# controller.net
KiCad netlist of a schematic drawn in Altium Designer
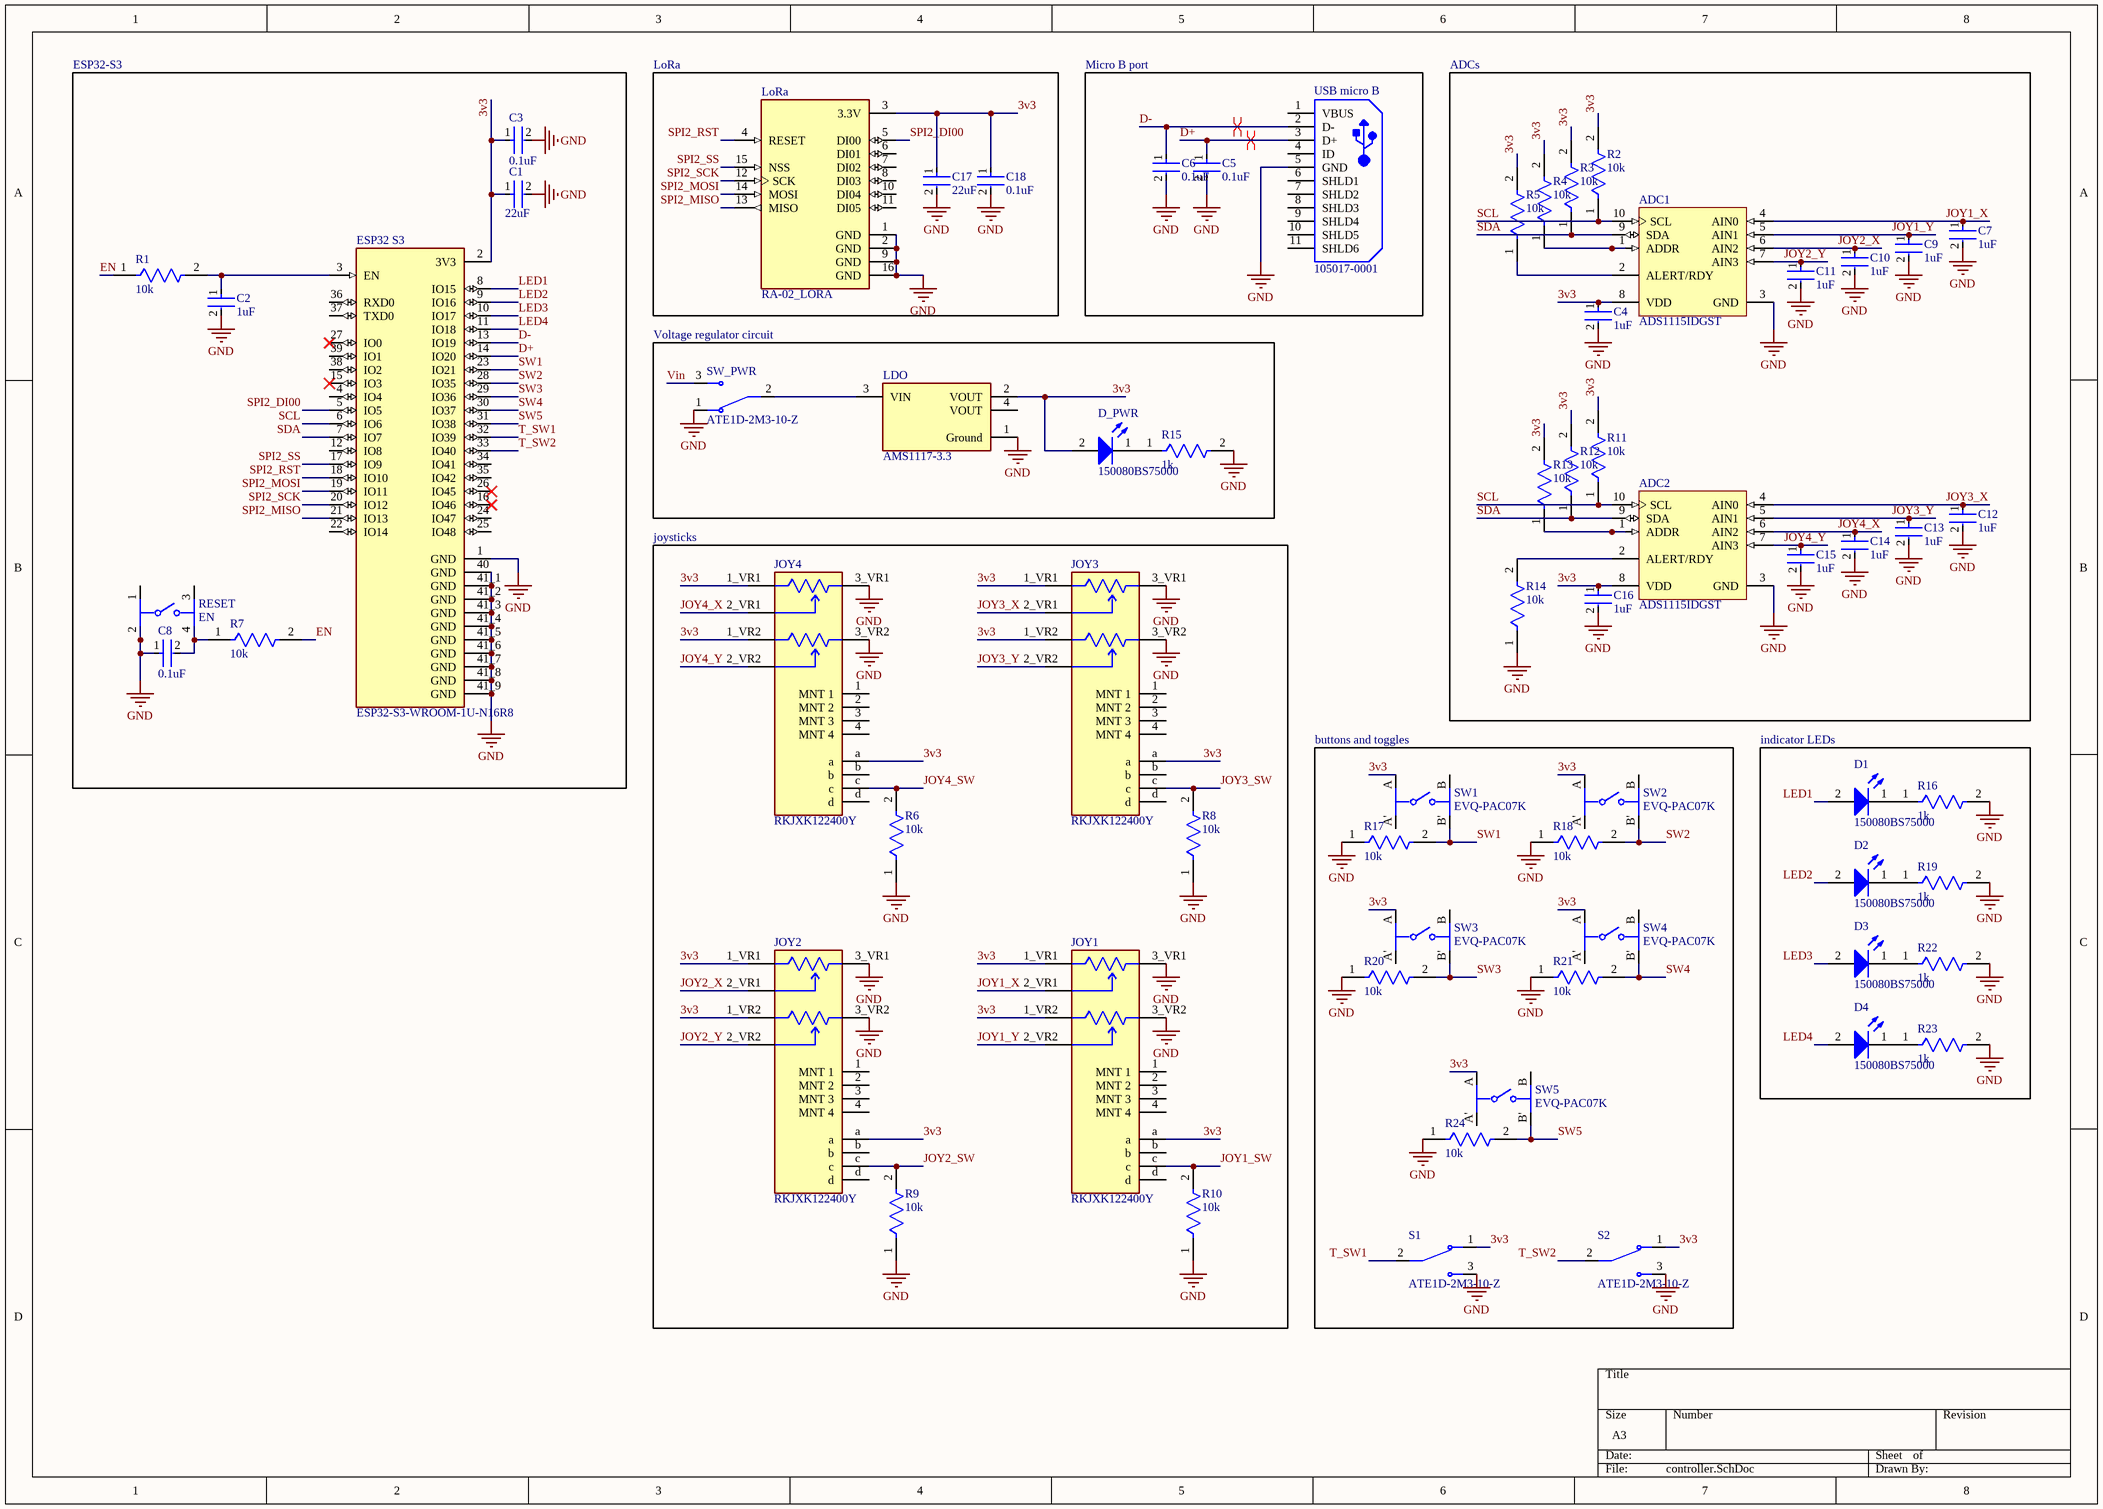
[diagram p0: controller.SchDoc]

(export (version "E")
  (design (tool "Eeschema 10.0.6"))
  (components
    (comp (ref "ADC1")
      (value "ADS1115IDGST")
      (footprint "TI-DGS10_M")
      (fields (field (name "MANUFACTURER") "Texas Instruments"))
      (libsource (lib "Altium Content Vault") (part "TI-ADS1015_1115-10"))
    )
    (comp (ref "ADC2")
      (value "ADS1115IDGST")
      (footprint "TI-DGS10_M")
      (fields (field (name "MANUFACTURER") "Texas Instruments"))
      (libsource (lib "Altium Content Vault") (part "TI-ADS1015_1115-10"))
    )
    (comp (ref "C1")
      (value "22uF")
      (footprint "FP-0805-L_2_01_0_2-W_1_25-IPC_B")
      (description "General Purpose Ceramic Capacitor, 0805, 22uF, 20%, X5R, 15%, 6.3V")
      (fields (field (name "TOLERANCE") "20%") (field (name "VOLTAGE") "6.3V"))
      (libsource (lib "Altium Content Vault") (part "02cd4be3c70576c341d710602a673aa"))
    )
    (comp (ref "C2")
      (value "1uF")
      (footprint "FP-0805-L_2_01_0_2-W_1_25-IPC_B")
      (description "General Purpose Ceramic Capacitor, 0805, 1uF, 10%, X7R, 15%, 25V")
      (fields (field (name "TOLERANCE") "10%") (field (name "VOLTAGE") "25V"))
      (libsource (lib "Altium Content Vault") (part "b4654b650e69147ec39a6b967a45e02"))
    )
    (comp (ref "C3")
      (value "0.1uF")
      (footprint "FP-0805-L_2_01_0_2-W_1_25-IPC_C")
      (description "General Purpose Ceramic Capacitor, 0805, 100nF, 10%, X7R, 0.15, 50V")
      (fields (field (name "TOLERANCE") "10%") (field (name "VOLTAGE") "50V"))
      (libsource (lib "Altium Content Vault") (part "02cd4be3c70576c341d710602a673aa"))
    )
    (comp (ref "C4")
      (value "1uF")
      (footprint "FP-0805-L_2_01_0_2-W_1_25-IPC_B")
      (description "General Purpose Ceramic Capacitor, 0805, 1uF, 10%, X7R, 15%, 25V")
      (fields (field (name "TOLERANCE") "10%") (field (name "VOLTAGE") "25V"))
      (libsource (lib "Altium Content Vault") (part "b4654b650e69147ec39a6b967a45e02"))
    )
    (comp (ref "C5")
      (value "0.1uF")
      (footprint "FP-0805-L_2_01_0_2-W_1_25-IPC_C")
      (description "General Purpose Ceramic Capacitor, 0805, 100nF, 10%, X7R, 0.15, 50V")
      (fields (field (name "TOLERANCE") "10%") (field (name "VOLTAGE") "50V"))
      (libsource (lib "Altium Content Vault") (part "02cd4be3c70576c341d710602a673aa"))
    )
    (comp (ref "C6")
      (value "0.1uF")
      (footprint "FP-0805-L_2_01_0_2-W_1_25-IPC_C")
      (description "General Purpose Ceramic Capacitor, 0805, 100nF, 10%, X7R, 0.15, 50V")
      (fields (field (name "TOLERANCE") "10%") (field (name "VOLTAGE") "50V"))
      (libsource (lib "Altium Content Vault") (part "02cd4be3c70576c341d710602a673aa"))
    )
    (comp (ref "C7")
      (value "1uF")
      (footprint "FP-0805-L_2_01_0_2-W_1_25-IPC_B")
      (description "General Purpose Ceramic Capacitor, 0805, 1uF, 10%, X7R, 15%, 25V")
      (fields (field (name "TOLERANCE") "10%") (field (name "VOLTAGE") "25V"))
      (libsource (lib "Altium Content Vault") (part "b4654b650e69147ec39a6b967a45e02"))
    )
    (comp (ref "C8")
      (value "0.1uF")
      (footprint "FP-0805-L_2_01_0_2-W_1_25-IPC_C")
      (description "General Purpose Ceramic Capacitor, 0805, 100nF, 10%, X7R, 0.15, 50V")
      (fields (field (name "TOLERANCE") "10%") (field (name "VOLTAGE") "50V"))
      (libsource (lib "Altium Content Vault") (part "02cd4be3c70576c341d710602a673aa"))
    )
    (comp (ref "C9")
      (value "1uF")
      (footprint "FP-0805-L_2_01_0_2-W_1_25-IPC_B")
      (description "General Purpose Ceramic Capacitor, 0805, 1uF, 10%, X7R, 15%, 25V")
      (fields (field (name "TOLERANCE") "10%") (field (name "VOLTAGE") "25V"))
      (libsource (lib "Altium Content Vault") (part "b4654b650e69147ec39a6b967a45e02"))
    )
    (comp (ref "C10")
      (value "1uF")
      (footprint "FP-0805-L_2_01_0_2-W_1_25-IPC_B")
      (description "General Purpose Ceramic Capacitor, 0805, 1uF, 10%, X7R, 15%, 25V")
      (fields (field (name "TOLERANCE") "10%") (field (name "VOLTAGE") "25V"))
      (libsource (lib "Altium Content Vault") (part "b4654b650e69147ec39a6b967a45e02"))
    )
    (comp (ref "C11")
      (value "1uF")
      (footprint "FP-0805-L_2_01_0_2-W_1_25-IPC_B")
      (description "General Purpose Ceramic Capacitor, 0805, 1uF, 10%, X7R, 15%, 25V")
      (fields (field (name "TOLERANCE") "10%") (field (name "VOLTAGE") "25V"))
      (libsource (lib "Altium Content Vault") (part "b4654b650e69147ec39a6b967a45e02"))
    )
    (comp (ref "C12")
      (value "1uF")
      (footprint "FP-0805-L_2_01_0_2-W_1_25-IPC_B")
      (description "General Purpose Ceramic Capacitor, 0805, 1uF, 10%, X7R, 15%, 25V")
      (fields (field (name "TOLERANCE") "10%") (field (name "VOLTAGE") "25V"))
      (libsource (lib "Altium Content Vault") (part "b4654b650e69147ec39a6b967a45e02"))
    )
    (comp (ref "C13")
      (value "1uF")
      (footprint "FP-0805-L_2_01_0_2-W_1_25-IPC_B")
      (description "General Purpose Ceramic Capacitor, 0805, 1uF, 10%, X7R, 15%, 25V")
      (fields (field (name "TOLERANCE") "10%") (field (name "VOLTAGE") "25V"))
      (libsource (lib "Altium Content Vault") (part "b4654b650e69147ec39a6b967a45e02"))
    )
    (comp (ref "C14")
      (value "1uF")
      (footprint "FP-0805-L_2_01_0_2-W_1_25-IPC_B")
      (description "General Purpose Ceramic Capacitor, 0805, 1uF, 10%, X7R, 15%, 25V")
      (fields (field (name "TOLERANCE") "10%") (field (name "VOLTAGE") "25V"))
      (libsource (lib "Altium Content Vault") (part "b4654b650e69147ec39a6b967a45e02"))
    )
    (comp (ref "C15")
      (value "1uF")
      (footprint "FP-0805-L_2_01_0_2-W_1_25-IPC_B")
      (description "General Purpose Ceramic Capacitor, 0805, 1uF, 10%, X7R, 15%, 25V")
      (fields (field (name "TOLERANCE") "10%") (field (name "VOLTAGE") "25V"))
      (libsource (lib "Altium Content Vault") (part "b4654b650e69147ec39a6b967a45e02"))
    )
    (comp (ref "C16")
      (value "1uF")
      (footprint "FP-0805-L_2_01_0_2-W_1_25-IPC_B")
      (description "General Purpose Ceramic Capacitor, 0805, 1uF, 10%, X7R, 15%, 25V")
      (fields (field (name "TOLERANCE") "10%") (field (name "VOLTAGE") "25V"))
      (libsource (lib "Altium Content Vault") (part "b4654b650e69147ec39a6b967a45e02"))
    )
    (comp (ref "C17")
      (value "22uF")
      (footprint "FP-0805-L_2_01_0_2-W_1_25-IPC_B")
      (description "General Purpose Ceramic Capacitor, 0805, 22uF, 20%, X5R, 15%, 6.3V")
      (fields (field (name "TOLERANCE") "20%") (field (name "VOLTAGE") "6.3V"))
      (libsource (lib "Altium Content Vault") (part "02cd4be3c70576c341d710602a673aa"))
    )
    (comp (ref "C18")
      (value "0.1uF")
      (footprint "FP-0805-L_2_01_0_2-W_1_25-IPC_C")
      (description "General Purpose Ceramic Capacitor, 0805, 100nF, 10%, X7R, 0.15, 50V")
      (fields (field (name "TOLERANCE") "10%") (field (name "VOLTAGE") "50V"))
      (libsource (lib "Altium Content Vault") (part "02cd4be3c70576c341d710602a673aa"))
    )
    (comp (ref "D1")
      (value "150080BS75000")
      (footprint "WL-SMCW_0805_150080xx75000")
      (description "Led, Blue, 470 Nm, 3.2 V, 30 Ma, 145 Mcd Rohs Compliant: Yes")
      (libsource (lib "Altium Content Vault") (part "LED_Blue_2A-1K"))
    )
    (comp (ref "D2")
      (value "150080BS75000")
      (footprint "WL-SMCW_0805_150080xx75000")
      (description "Led, Blue, 470 Nm, 3.2 V, 30 Ma, 145 Mcd Rohs Compliant: Yes")
      (libsource (lib "Altium Content Vault") (part "LED_Blue_2A-1K"))
    )
    (comp (ref "D3")
      (value "150080BS75000")
      (footprint "WL-SMCW_0805_150080xx75000")
      (description "Led, Blue, 470 Nm, 3.2 V, 30 Ma, 145 Mcd Rohs Compliant: Yes")
      (libsource (lib "Altium Content Vault") (part "LED_Blue_2A-1K"))
    )
    (comp (ref "D4")
      (value "150080BS75000")
      (footprint "WL-SMCW_0805_150080xx75000")
      (description "Led, Blue, 470 Nm, 3.2 V, 30 Ma, 145 Mcd Rohs Compliant: Yes")
      (libsource (lib "Altium Content Vault") (part "LED_Blue_2A-1K"))
    )
    (comp (ref "D_PWR")
      (value "150080BS75000")
      (footprint "WL-SMCW_0805_150080xx75000")
      (description "Led, Blue, 470 Nm, 3.2 V, 30 Ma, 145 Mcd Rohs Compliant: Yes")
      (libsource (lib "Altium Content Vault") (part "LED_Blue_2A-1K"))
    )
    (comp (ref "ESP32 S3")
      (value "ESP32-S3-WROOM-1U-N16R8")
      (footprint "XCVR_ESP32-S3-WROOM-1U-N16R8")
      (fields (field (name "MF") "Espressif Systems"))
      (libsource (lib "ESP32-S3-WROOM-1U-N16R8") (part "ESP32-S3-WROOM-1U-N16R8"))
    )
    (comp (ref "JOY1")
      (value "RKJXK122400Y")
      (footprint "FP-RKJXK122400Y-MFG")
      (description "Res POT 10K Ohm 0.0125W (25.4 X 20.7 X 19.3mm) Pin Bracket Mount/Through Hole Tray")
      (libsource (lib "Altium Content Vault") (part "63a56dd8e99e1e1552a3870b2e96c5c"))
    )
    (comp (ref "JOY2")
      (value "RKJXK122400Y")
      (footprint "FP-RKJXK122400Y-MFG")
      (description "Res POT 10K Ohm 0.0125W (25.4 X 20.7 X 19.3mm) Pin Bracket Mount/Through Hole Tray")
      (libsource (lib "Altium Content Vault") (part "63a56dd8e99e1e1552a3870b2e96c5c"))
    )
    (comp (ref "JOY3")
      (value "RKJXK122400Y")
      (footprint "FP-RKJXK122400Y-MFG")
      (description "Res POT 10K Ohm 0.0125W (25.4 X 20.7 X 19.3mm) Pin Bracket Mount/Through Hole Tray")
      (libsource (lib "Altium Content Vault") (part "63a56dd8e99e1e1552a3870b2e96c5c"))
    )
    (comp (ref "JOY4")
      (value "RKJXK122400Y")
      (footprint "FP-RKJXK122400Y-MFG")
      (description "Res POT 10K Ohm 0.0125W (25.4 X 20.7 X 19.3mm) Pin Bracket Mount/Through Hole Tray")
      (libsource (lib "Altium Content Vault") (part "63a56dd8e99e1e1552a3870b2e96c5c"))
    )
    (comp (ref "LDO")
      (value "AMS1117-3.3")
      (footprint "FP-AMS1117-IPC_C")
      (description "LDO Voltage Regulators 1A, 3.3V")
      (fields
        (field (name "OCTOPART") "https://octopart.com/ams1117-3.3-advanced+monolithic+systems-25899300")
        (field (name "MANUFACTURER") "Advanced Monolithic Systems")
      )
      (libsource (lib "Altium Content Vault") (part "8bdbb5f8e77002000e30dd2845d0354"))
    )
    (comp (ref "LoRa")
      (value "RA-02_LORA")
      (footprint "MODULE_RA-02_LORA")
      (description "Ra-02 LoRa RF M5Stack Platform Evaluation Expansion Board")
      (libsource (lib "RA-02_LORA") (part "RA-02_LORA"))
    )
    (comp (ref "R1")
      (value "10k")
      (footprint "FP-CRCW0805-e3-IPC_A")
      (description "RES Thick Film, 10kΩ, 1%, 0.125W, 100ppm/°C, 0805")
      (fields (field (name "TOLERANCE") "1%"))
      (libsource (lib "Altium Content Vault") (part "1029c3af85768c4190bb7ad29bc67b5"))
    )
    (comp (ref "R2")
      (value "10k")
      (footprint "FP-CRCW0805-e3-IPC_A")
      (description "RES Thick Film, 10kΩ, 1%, 0.125W, 100ppm/°C, 0805")
      (fields (field (name "TOLERANCE") "1%"))
      (libsource (lib "Altium Content Vault") (part "1029c3af85768c4190bb7ad29bc67b5"))
    )
    (comp (ref "R3")
      (value "10k")
      (footprint "FP-CRCW0805-e3-IPC_A")
      (description "RES Thick Film, 10kΩ, 1%, 0.125W, 100ppm/°C, 0805")
      (fields (field (name "TOLERANCE") "1%"))
      (libsource (lib "Altium Content Vault") (part "1029c3af85768c4190bb7ad29bc67b5"))
    )
    (comp (ref "R4")
      (value "10k")
      (footprint "FP-CRCW0805-e3-IPC_A")
      (description "RES Thick Film, 10kΩ, 1%, 0.125W, 100ppm/°C, 0805")
      (fields (field (name "TOLERANCE") "1%"))
      (libsource (lib "Altium Content Vault") (part "1029c3af85768c4190bb7ad29bc67b5"))
    )
    (comp (ref "R5")
      (value "10k")
      (footprint "FP-CRCW0805-e3-IPC_A")
      (description "RES Thick Film, 10kΩ, 1%, 0.125W, 100ppm/°C, 0805")
      (fields (field (name "TOLERANCE") "1%"))
      (libsource (lib "Altium Content Vault") (part "1029c3af85768c4190bb7ad29bc67b5"))
    )
    (comp (ref "R6")
      (value "10k")
      (footprint "FP-CRCW0805-e3-IPC_A")
      (description "RES Thick Film, 10kΩ, 1%, 0.125W, 100ppm/°C, 0805")
      (fields (field (name "TOLERANCE") "1%"))
      (libsource (lib "Altium Content Vault") (part "1029c3af85768c4190bb7ad29bc67b5"))
    )
    (comp (ref "R7")
      (value "10k")
      (footprint "FP-CRCW0805-e3-IPC_A")
      (description "RES Thick Film, 10kΩ, 1%, 0.125W, 100ppm/°C, 0805")
      (fields (field (name "TOLERANCE") "1%"))
      (libsource (lib "Altium Content Vault") (part "1029c3af85768c4190bb7ad29bc67b5"))
    )
    (comp (ref "R8")
      (value "10k")
      (footprint "FP-CRCW0805-e3-IPC_A")
      (description "RES Thick Film, 10kΩ, 1%, 0.125W, 100ppm/°C, 0805")
      (fields (field (name "TOLERANCE") "1%"))
      (libsource (lib "Altium Content Vault") (part "1029c3af85768c4190bb7ad29bc67b5"))
    )
    (comp (ref "R9")
      (value "10k")
      (footprint "FP-CRCW0805-e3-IPC_A")
      (description "RES Thick Film, 10kΩ, 1%, 0.125W, 100ppm/°C, 0805")
      (fields (field (name "TOLERANCE") "1%"))
      (libsource (lib "Altium Content Vault") (part "1029c3af85768c4190bb7ad29bc67b5"))
    )
    (comp (ref "R10")
      (value "10k")
      (footprint "FP-CRCW0805-e3-IPC_A")
      (description "RES Thick Film, 10kΩ, 1%, 0.125W, 100ppm/°C, 0805")
      (fields (field (name "TOLERANCE") "1%"))
      (libsource (lib "Altium Content Vault") (part "1029c3af85768c4190bb7ad29bc67b5"))
    )
    (comp (ref "R11")
      (value "10k")
      (footprint "FP-CRCW0805-e3-IPC_A")
      (description "RES Thick Film, 10kΩ, 1%, 0.125W, 100ppm/°C, 0805")
      (fields (field (name "TOLERANCE") "1%"))
      (libsource (lib "Altium Content Vault") (part "1029c3af85768c4190bb7ad29bc67b5"))
    )
    (comp (ref "R12")
      (value "10k")
      (footprint "FP-CRCW0805-e3-IPC_A")
      (description "RES Thick Film, 10kΩ, 1%, 0.125W, 100ppm/°C, 0805")
      (fields (field (name "TOLERANCE") "1%"))
      (libsource (lib "Altium Content Vault") (part "1029c3af85768c4190bb7ad29bc67b5"))
    )
    (comp (ref "R13")
      (value "10k")
      (footprint "FP-CRCW0805-e3-IPC_A")
      (description "RES Thick Film, 10kΩ, 1%, 0.125W, 100ppm/°C, 0805")
      (fields (field (name "TOLERANCE") "1%"))
      (libsource (lib "Altium Content Vault") (part "1029c3af85768c4190bb7ad29bc67b5"))
    )
    (comp (ref "R14")
      (value "10k")
      (footprint "FP-CRCW0805-e3-IPC_A")
      (description "RES Thick Film, 10kΩ, 1%, 0.125W, 100ppm/°C, 0805")
      (fields (field (name "TOLERANCE") "1%"))
      (libsource (lib "Altium Content Vault") (part "1029c3af85768c4190bb7ad29bc67b5"))
    )
    (comp (ref "R15")
      (value "1k")
      (footprint "FP-CRCW0805-e3-MFG")
      (description "RES Thick Film, 1.2kΩ, 1%, 0.125W, 100ppm/°C, 0805")
      (fields (field (name "TOLERANCE") "1%"))
      (libsource (lib "Altium Content Vault") (part "1029c3af85768c4190bb7ad29bc67b5"))
    )
    (comp (ref "R16")
      (value "1k")
      (footprint "FP-CRCW0805-e3-MFG")
      (description "RES Thick Film, 1.2kΩ, 1%, 0.125W, 100ppm/°C, 0805")
      (fields (field (name "TOLERANCE") "1%"))
      (libsource (lib "Altium Content Vault") (part "1029c3af85768c4190bb7ad29bc67b5"))
    )
    (comp (ref "R17")
      (value "10k")
      (footprint "FP-CRCW0805-e3-IPC_A")
      (description "RES Thick Film, 10kΩ, 1%, 0.125W, 100ppm/°C, 0805")
      (fields (field (name "TOLERANCE") "1%"))
      (libsource (lib "Altium Content Vault") (part "1029c3af85768c4190bb7ad29bc67b5"))
    )
    (comp (ref "R18")
      (value "10k")
      (footprint "FP-CRCW0805-e3-IPC_A")
      (description "RES Thick Film, 10kΩ, 1%, 0.125W, 100ppm/°C, 0805")
      (fields (field (name "TOLERANCE") "1%"))
      (libsource (lib "Altium Content Vault") (part "1029c3af85768c4190bb7ad29bc67b5"))
    )
    (comp (ref "R19")
      (value "1k")
      (footprint "FP-CRCW0805-e3-MFG")
      (description "RES Thick Film, 1.2kΩ, 1%, 0.125W, 100ppm/°C, 0805")
      (fields (field (name "TOLERANCE") "1%"))
      (libsource (lib "Altium Content Vault") (part "1029c3af85768c4190bb7ad29bc67b5"))
    )
    (comp (ref "R20")
      (value "10k")
      (footprint "FP-CRCW0805-e3-IPC_A")
      (description "RES Thick Film, 10kΩ, 1%, 0.125W, 100ppm/°C, 0805")
      (fields (field (name "TOLERANCE") "1%"))
      (libsource (lib "Altium Content Vault") (part "1029c3af85768c4190bb7ad29bc67b5"))
    )
    (comp (ref "R21")
      (value "10k")
      (footprint "FP-CRCW0805-e3-IPC_A")
      (description "RES Thick Film, 10kΩ, 1%, 0.125W, 100ppm/°C, 0805")
      (fields (field (name "TOLERANCE") "1%"))
      (libsource (lib "Altium Content Vault") (part "1029c3af85768c4190bb7ad29bc67b5"))
    )
    (comp (ref "R22")
      (value "1k")
      (footprint "FP-CRCW0805-e3-MFG")
      (description "RES Thick Film, 1.2kΩ, 1%, 0.125W, 100ppm/°C, 0805")
      (fields (field (name "TOLERANCE") "1%"))
      (libsource (lib "Altium Content Vault") (part "1029c3af85768c4190bb7ad29bc67b5"))
    )
    (comp (ref "R23")
      (value "1k")
      (footprint "FP-CRCW0805-e3-MFG")
      (description "RES Thick Film, 1.2kΩ, 1%, 0.125W, 100ppm/°C, 0805")
      (fields (field (name "TOLERANCE") "1%"))
      (libsource (lib "Altium Content Vault") (part "1029c3af85768c4190bb7ad29bc67b5"))
    )
    (comp (ref "R24")
      (value "10k")
      (footprint "FP-CRCW0805-e3-IPC_A")
      (description "RES Thick Film, 10kΩ, 1%, 0.125W, 100ppm/°C, 0805")
      (fields (field (name "TOLERANCE") "1%"))
      (libsource (lib "Altium Content Vault") (part "1029c3af85768c4190bb7ad29bc67b5"))
    )
    (comp (ref "RESET")
      (value "EN")
      (footprint "FP-FSM2JSMAA-MFG")
      (description "SWITCH TACTILE SPST-NO 0.05A 24V")
      (fields
        (field (name "MANUFACTURER PART NUMBER") "FSM2JSMAA")
        (field (name "MANUFACTURER") "TE Connectivity")
      )
      (libsource (lib "Altium Content Vault") (part "b8895f3f4cefb76e1819d2863dba89b"))
    )
    (comp (ref "S1")
      (value "ATE1D-2M3-10-Z")
      (footprint "SW_ATE1D-2M3-10-Z")
      (description "Toggle Switch SPDT Through Hole")
      (fields
        (field (name "MF") "Nidec Copal Electronics")
        (field (name "DIGI-KEY_PART_NUMBER") "563-1157-ND")
      )
      (libsource (lib "ATE1D-2M3-10-Z") (part "ATE1D-2M3-10-Z"))
    )
    (comp (ref "S2")
      (value "ATE1D-2M3-10-Z")
      (footprint "SW_ATE1D-2M3-10-Z")
      (description "Toggle Switch SPDT Through Hole")
      (fields
        (field (name "MF") "Nidec Copal Electronics")
        (field (name "DIGI-KEY_PART_NUMBER") "563-1157-ND")
      )
      (libsource (lib "ATE1D-2M3-10-Z") (part "ATE1D-2M3-10-Z"))
    )
    (comp (ref "SW1")
      (value "EVQ-PAC07K")
      (footprint "FP-EVQ-PAC07K-MFG")
      (description "EVQ-PAC07K Switch Tactile N.O. SPST Round Button PC Pins 0.02A 15VDC 1N Thru-Hole Bulk")
      (libsource (lib "Altium Content Vault") (part "841f23923f71b23f3ea0ab5dfb78dcc"))
    )
    (comp (ref "SW2")
      (value "EVQ-PAC07K")
      (footprint "FP-EVQ-PAC07K-MFG")
      (description "EVQ-PAC07K Switch Tactile N.O. SPST Round Button PC Pins 0.02A 15VDC 1N Thru-Hole Bulk")
      (libsource (lib "Altium Content Vault") (part "841f23923f71b23f3ea0ab5dfb78dcc"))
    )
    (comp (ref "SW3")
      (value "EVQ-PAC07K")
      (footprint "FP-EVQ-PAC07K-MFG")
      (description "EVQ-PAC07K Switch Tactile N.O. SPST Round Button PC Pins 0.02A 15VDC 1N Thru-Hole Bulk")
      (libsource (lib "Altium Content Vault") (part "841f23923f71b23f3ea0ab5dfb78dcc"))
    )
    (comp (ref "SW4")
      (value "EVQ-PAC07K")
      (footprint "FP-EVQ-PAC07K-MFG")
      (description "EVQ-PAC07K Switch Tactile N.O. SPST Round Button PC Pins 0.02A 15VDC 1N Thru-Hole Bulk")
      (libsource (lib "Altium Content Vault") (part "841f23923f71b23f3ea0ab5dfb78dcc"))
    )
    (comp (ref "SW5")
      (value "EVQ-PAC07K")
      (footprint "FP-EVQ-PAC07K-MFG")
      (description "EVQ-PAC07K Switch Tactile N.O. SPST Round Button PC Pins 0.02A 15VDC 1N Thru-Hole Bulk")
      (libsource (lib "Altium Content Vault") (part "841f23923f71b23f3ea0ab5dfb78dcc"))
    )
    (comp (ref "SW_PWR")
      (value "ATE1D-2M3-10-Z")
      (footprint "SW_ATE1D-2M3-10-Z")
      (description "Toggle Switch SPDT Through Hole")
      (fields
        (field (name "MF") "Nidec Copal Electronics")
        (field (name "DIGI-KEY_PART_NUMBER") "563-1157-ND")
      )
      (libsource (lib "ATE1D-2M3-10-Z") (part "ATE1D-2M3-10-Z"))
    )
    (comp (ref "USB micro B")
      (value "105017-0001")
      (footprint "USB-MICRO-B_V")
      (fields (field (name "MANUFACTURER") "Molex"))
      (libsource (lib "Altium Content Vault") (part "USB-5-6SHLD"))
    )
  )
  (nets
    (net (code "1") (name "/3v3") (class "Default")
      (node (ref "ADC1") (pin "8") (pinfunction "VDD_8") (pintype "power_in"))
      (node (ref "ADC2") (pin "8") (pinfunction "VDD_8") (pintype "power_in"))
      (node (ref "C1") (pin "1") (pinfunction "1_1") (pintype "passive"))
      (node (ref "C16") (pin "1") (pinfunction "1_1") (pintype "passive"))
      (node (ref "C17") (pin "1") (pinfunction "1_1") (pintype "passive"))
      (node (ref "C18") (pin "1") (pinfunction "1_1") (pintype "passive"))
      (node (ref "C3") (pin "1") (pinfunction "1_1") (pintype "passive"))
      (node (ref "C4") (pin "1") (pinfunction "1_1") (pintype "passive"))
      (node (ref "D_PWR") (pin "2") (pinfunction "A_2") (pintype "passive"))
      (node (ref "ESP32 S3") (pin "2") (pinfunction "3V3_2") (pintype "power_in"))
      (node (ref "JOY1") (pin "1_VR1") (pinfunction "1_VR1_1_VR1") (pintype "passive"))
      (node (ref "JOY1") (pin "1_VR2") (pinfunction "1_VR2_1_VR2") (pintype "passive"))
      (node (ref "JOY1") (pin "a") (pinfunction "a_a") (pintype "passive"))
      (node (ref "JOY2") (pin "1_VR1") (pinfunction "1_VR1_1_VR1") (pintype "passive"))
      (node (ref "JOY2") (pin "1_VR2") (pinfunction "1_VR2_1_VR2") (pintype "passive"))
      (node (ref "JOY2") (pin "a") (pinfunction "a_a") (pintype "passive"))
      (node (ref "JOY3") (pin "1_VR1") (pinfunction "1_VR1_1_VR1") (pintype "passive"))
      (node (ref "JOY3") (pin "1_VR2") (pinfunction "1_VR2_1_VR2") (pintype "passive"))
      (node (ref "JOY3") (pin "a") (pinfunction "a_a") (pintype "passive"))
      (node (ref "JOY4") (pin "1_VR1") (pinfunction "1_VR1_1_VR1") (pintype "passive"))
      (node (ref "JOY4") (pin "1_VR2") (pinfunction "1_VR2_1_VR2") (pintype "passive"))
      (node (ref "JOY4") (pin "a") (pinfunction "a_a") (pintype "passive"))
      (node (ref "LDO") (pin "2") (pinfunction "VOUT_2") (pintype "passive"))
      (node (ref "LoRa") (pin "3") (pinfunction "3.3V_3") (pintype "power_in"))
      (node (ref "R11") (pin "2") (pinfunction "2_2") (pintype "passive"))
      (node (ref "R12") (pin "2") (pinfunction "2_2") (pintype "passive"))
      (node (ref "R13") (pin "2") (pinfunction "2_2") (pintype "passive"))
      (node (ref "R2") (pin "2") (pinfunction "2_2") (pintype "passive"))
      (node (ref "R3") (pin "2") (pinfunction "2_2") (pintype "passive"))
      (node (ref "R4") (pin "2") (pinfunction "2_2") (pintype "passive"))
      (node (ref "R5") (pin "2") (pinfunction "2_2") (pintype "passive"))
      (node (ref "S1") (pin "1") (pinfunction "1_1") (pintype "passive"))
      (node (ref "S2") (pin "1") (pinfunction "1_1") (pintype "passive"))
      (node (ref "SW1") (pin "A") (pinfunction "A_A") (pintype "passive"))
      (node (ref "SW2") (pin "A") (pinfunction "A_A") (pintype "passive"))
      (node (ref "SW3") (pin "A") (pinfunction "A_A") (pintype "passive"))
      (node (ref "SW4") (pin "A") (pinfunction "A_A") (pintype "passive"))
      (node (ref "SW5") (pin "A") (pinfunction "A_A") (pintype "passive"))
    )
    (net (code "2") (name "/D+") (class "Default")
      (node (ref "C5") (pin "1") (pinfunction "1_1") (pintype "passive"))
      (node (ref "ESP32 S3") (pin "14") (pinfunction "IO20_14") (pintype "bidirectional"))
      (node (ref "USB micro B") (pin "3") (pinfunction "D+_3") (pintype "passive"))
    )
    (net (code "3") (name "/D-") (class "Default")
      (node (ref "C6") (pin "1") (pinfunction "1_1") (pintype "passive"))
      (node (ref "ESP32 S3") (pin "13") (pinfunction "IO19_13") (pintype "bidirectional"))
      (node (ref "USB micro B") (pin "2") (pinfunction "D-_2") (pintype "passive"))
    )
    (net (code "4") (name "/EN") (class "Default")
      (node (ref "R1") (pin "1") (pinfunction "1_1") (pintype "passive"))
      (node (ref "R7") (pin "2") (pinfunction "2_2") (pintype "passive"))
    )
    (net (code "5") (name "/JOY1_SW") (class "Default")
      (node (ref "JOY1") (pin "c") (pinfunction "c_c") (pintype "passive"))
      (node (ref "R10") (pin "2") (pinfunction "2_2") (pintype "passive"))
    )
    (net (code "6") (name "/JOY1_X") (class "Default")
      (node (ref "ADC1") (pin "4") (pinfunction "AIN0_4") (pintype "input"))
      (node (ref "C7") (pin "1") (pinfunction "1_1") (pintype "passive"))
      (node (ref "JOY1") (pin "2_VR1") (pinfunction "2_VR1_2_VR1") (pintype "passive"))
    )
    (net (code "7") (name "/JOY1_Y") (class "Default")
      (node (ref "ADC1") (pin "5") (pinfunction "AIN1_5") (pintype "input"))
      (node (ref "C9") (pin "1") (pinfunction "1_1") (pintype "passive"))
      (node (ref "JOY1") (pin "2_VR2") (pinfunction "2_VR2_2_VR2") (pintype "passive"))
    )
    (net (code "8") (name "/JOY2_SW") (class "Default")
      (node (ref "JOY2") (pin "c") (pinfunction "c_c") (pintype "passive"))
      (node (ref "R9") (pin "2") (pinfunction "2_2") (pintype "passive"))
    )
    (net (code "9") (name "/JOY2_X") (class "Default")
      (node (ref "ADC1") (pin "6") (pinfunction "AIN2_6") (pintype "input"))
      (node (ref "C10") (pin "1") (pinfunction "1_1") (pintype "passive"))
      (node (ref "JOY2") (pin "2_VR1") (pinfunction "2_VR1_2_VR1") (pintype "passive"))
    )
    (net (code "10") (name "/JOY2_Y") (class "Default")
      (node (ref "ADC1") (pin "7") (pinfunction "AIN3_7") (pintype "input"))
      (node (ref "C11") (pin "1") (pinfunction "1_1") (pintype "passive"))
      (node (ref "JOY2") (pin "2_VR2") (pinfunction "2_VR2_2_VR2") (pintype "passive"))
    )
    (net (code "11") (name "/JOY3_SW") (class "Default")
      (node (ref "JOY3") (pin "c") (pinfunction "c_c") (pintype "passive"))
      (node (ref "R8") (pin "2") (pinfunction "2_2") (pintype "passive"))
    )
    (net (code "12") (name "/JOY3_X") (class "Default")
      (node (ref "ADC2") (pin "4") (pinfunction "AIN0_4") (pintype "input"))
      (node (ref "C12") (pin "1") (pinfunction "1_1") (pintype "passive"))
      (node (ref "JOY3") (pin "2_VR1") (pinfunction "2_VR1_2_VR1") (pintype "passive"))
    )
    (net (code "13") (name "/JOY3_Y") (class "Default")
      (node (ref "ADC2") (pin "5") (pinfunction "AIN1_5") (pintype "input"))
      (node (ref "C13") (pin "1") (pinfunction "1_1") (pintype "passive"))
      (node (ref "JOY3") (pin "2_VR2") (pinfunction "2_VR2_2_VR2") (pintype "passive"))
    )
    (net (code "14") (name "/JOY4_SW") (class "Default")
      (node (ref "JOY4") (pin "c") (pinfunction "c_c") (pintype "passive"))
      (node (ref "R6") (pin "2") (pinfunction "2_2") (pintype "passive"))
    )
    (net (code "15") (name "/JOY4_X") (class "Default")
      (node (ref "ADC2") (pin "6") (pinfunction "AIN2_6") (pintype "input"))
      (node (ref "C14") (pin "1") (pinfunction "1_1") (pintype "passive"))
      (node (ref "JOY4") (pin "2_VR1") (pinfunction "2_VR1_2_VR1") (pintype "passive"))
    )
    (net (code "16") (name "/JOY4_Y") (class "Default")
      (node (ref "ADC2") (pin "7") (pinfunction "AIN3_7") (pintype "input"))
      (node (ref "C15") (pin "1") (pinfunction "1_1") (pintype "passive"))
      (node (ref "JOY4") (pin "2_VR2") (pinfunction "2_VR2_2_VR2") (pintype "passive"))
    )
    (net (code "17") (name "/LED1") (class "Default")
      (node (ref "D1") (pin "2") (pinfunction "A_2") (pintype "passive"))
      (node (ref "ESP32 S3") (pin "8") (pinfunction "IO15_8") (pintype "bidirectional"))
    )
    (net (code "18") (name "/LED2") (class "Default")
      (node (ref "D2") (pin "2") (pinfunction "A_2") (pintype "passive"))
      (node (ref "ESP32 S3") (pin "9") (pinfunction "IO16_9") (pintype "bidirectional"))
    )
    (net (code "19") (name "/LED3") (class "Default")
      (node (ref "D3") (pin "2") (pinfunction "A_2") (pintype "passive"))
      (node (ref "ESP32 S3") (pin "10") (pinfunction "IO17_10") (pintype "bidirectional"))
    )
    (net (code "20") (name "/LED4") (class "Default")
      (node (ref "D4") (pin "2") (pinfunction "A_2") (pintype "passive"))
      (node (ref "ESP32 S3") (pin "11") (pinfunction "IO18_11") (pintype "bidirectional"))
    )
    (net (code "21") (name "/SCL") (class "Default")
      (node (ref "ADC1") (pin "10") (pinfunction "SCL_10") (pintype "input"))
      (node (ref "ADC2") (pin "10") (pinfunction "SCL_10") (pintype "input"))
      (node (ref "ESP32 S3") (pin "6") (pinfunction "IO6_6") (pintype "bidirectional"))
      (node (ref "R11") (pin "1") (pinfunction "1_1") (pintype "passive"))
      (node (ref "R2") (pin "1") (pinfunction "1_1") (pintype "passive"))
    )
    (net (code "22") (name "/SDA") (class "Default")
      (node (ref "ADC1") (pin "9") (pinfunction "SDA_9") (pintype "bidirectional"))
      (node (ref "ADC2") (pin "9") (pinfunction "SDA_9") (pintype "bidirectional"))
      (node (ref "ESP32 S3") (pin "7") (pinfunction "IO7_7") (pintype "bidirectional"))
      (node (ref "R12") (pin "1") (pinfunction "1_1") (pintype "passive"))
      (node (ref "R3") (pin "1") (pinfunction "1_1") (pintype "passive"))
    )
    (net (code "23") (name "/SPI2_DI00") (class "Default")
      (node (ref "ESP32 S3") (pin "5") (pinfunction "IO5_5") (pintype "bidirectional"))
      (node (ref "LoRa") (pin "5") (pinfunction "DI00_5") (pintype "bidirectional"))
    )
    (net (code "24") (name "/SPI2_MISO") (class "Default")
      (node (ref "ESP32 S3") (pin "21") (pinfunction "IO13_21") (pintype "bidirectional"))
      (node (ref "LoRa") (pin "13") (pinfunction "MISO_13") (pintype "output"))
    )
    (net (code "25") (name "/SPI2_MOSI") (class "Default")
      (node (ref "ESP32 S3") (pin "19") (pinfunction "IO11_19") (pintype "bidirectional"))
      (node (ref "LoRa") (pin "14") (pinfunction "MOSI_14") (pintype "input"))
    )
    (net (code "26") (name "/SPI2_RST") (class "Default")
      (node (ref "ESP32 S3") (pin "18") (pinfunction "IO10_18") (pintype "bidirectional"))
      (node (ref "LoRa") (pin "4") (pinfunction "RESET_4") (pintype "input"))
    )
    (net (code "27") (name "/SPI2_SCK") (class "Default")
      (node (ref "ESP32 S3") (pin "20") (pinfunction "IO12_20") (pintype "bidirectional"))
      (node (ref "LoRa") (pin "12") (pinfunction "SCK_12") (pintype "input"))
    )
    (net (code "28") (name "/SPI2_SS") (class "Default")
      (node (ref "ESP32 S3") (pin "17") (pinfunction "IO9_17") (pintype "bidirectional"))
      (node (ref "LoRa") (pin "15") (pinfunction "NSS_15") (pintype "input"))
    )
    (net (code "29") (name "/SW1") (class "Default")
      (node (ref "ESP32 S3") (pin "23") (pinfunction "IO21_23") (pintype "bidirectional"))
      (node (ref "R17") (pin "2") (pinfunction "2_2") (pintype "passive"))
      (node (ref "SW1") (pin "B'") (pinfunction "B'_B'") (pintype "passive"))
    )
    (net (code "30") (name "/SW2") (class "Default")
      (node (ref "ESP32 S3") (pin "28") (pinfunction "IO35_28") (pintype "bidirectional"))
      (node (ref "R18") (pin "2") (pinfunction "2_2") (pintype "passive"))
      (node (ref "SW2") (pin "B'") (pinfunction "B'_B'") (pintype "passive"))
    )
    (net (code "31") (name "/SW3") (class "Default")
      (node (ref "ESP32 S3") (pin "29") (pinfunction "IO36_29") (pintype "bidirectional"))
      (node (ref "R20") (pin "2") (pinfunction "2_2") (pintype "passive"))
      (node (ref "SW3") (pin "B'") (pinfunction "B'_B'") (pintype "passive"))
    )
    (net (code "32") (name "/SW4") (class "Default")
      (node (ref "ESP32 S3") (pin "30") (pinfunction "IO37_30") (pintype "bidirectional"))
      (node (ref "R21") (pin "2") (pinfunction "2_2") (pintype "passive"))
      (node (ref "SW4") (pin "B'") (pinfunction "B'_B'") (pintype "passive"))
    )
    (net (code "33") (name "/SW5") (class "Default")
      (node (ref "ESP32 S3") (pin "31") (pinfunction "IO38_31") (pintype "bidirectional"))
      (node (ref "R24") (pin "2") (pinfunction "2_2") (pintype "passive"))
      (node (ref "SW5") (pin "B'") (pinfunction "B'_B'") (pintype "passive"))
    )
    (net (code "34") (name "/T_SW1") (class "Default")
      (node (ref "ESP32 S3") (pin "32") (pinfunction "IO39_32") (pintype "bidirectional"))
      (node (ref "S1") (pin "2") (pinfunction "2_2") (pintype "passive"))
    )
    (net (code "35") (name "/T_SW2") (class "Default")
      (node (ref "ESP32 S3") (pin "33") (pinfunction "IO40_33") (pintype "bidirectional"))
      (node (ref "S2") (pin "2") (pinfunction "2_2") (pintype "passive"))
    )
    (net (code "36") (name "/Vin") (class "Default")
      (node (ref "SW_PWR") (pin "3") (pinfunction "3_3") (pintype "passive"))
    )
    (net (code "37") (name "GND") (class "Default")
      (node (ref "ADC1") (pin "3") (pinfunction "GND_3") (pintype "power_in"))
      (node (ref "ADC2") (pin "3") (pinfunction "GND_3") (pintype "power_in"))
      (node (ref "C1") (pin "2") (pinfunction "2_2") (pintype "passive"))
      (node (ref "C10") (pin "2") (pinfunction "2_2") (pintype "passive"))
      (node (ref "C11") (pin "2") (pinfunction "2_2") (pintype "passive"))
      (node (ref "C12") (pin "2") (pinfunction "2_2") (pintype "passive"))
      (node (ref "C13") (pin "2") (pinfunction "2_2") (pintype "passive"))
      (node (ref "C14") (pin "2") (pinfunction "2_2") (pintype "passive"))
      (node (ref "C15") (pin "2") (pinfunction "2_2") (pintype "passive"))
      (node (ref "C16") (pin "2") (pinfunction "2_2") (pintype "passive"))
      (node (ref "C17") (pin "2") (pinfunction "2_2") (pintype "passive"))
      (node (ref "C18") (pin "2") (pinfunction "2_2") (pintype "passive"))
      (node (ref "C2") (pin "2") (pinfunction "2_2") (pintype "passive"))
      (node (ref "C3") (pin "2") (pinfunction "2_2") (pintype "passive"))
      (node (ref "C4") (pin "2") (pinfunction "2_2") (pintype "passive"))
      (node (ref "C5") (pin "2") (pinfunction "2_2") (pintype "passive"))
      (node (ref "C6") (pin "2") (pinfunction "2_2") (pintype "passive"))
      (node (ref "C7") (pin "2") (pinfunction "2_2") (pintype "passive"))
      (node (ref "C8") (pin "1") (pinfunction "1_1") (pintype "passive"))
      (node (ref "C9") (pin "2") (pinfunction "2_2") (pintype "passive"))
      (node (ref "ESP32 S3") (pin "1") (pinfunction "GND_1") (pintype "power_in"))
      (node (ref "ESP32 S3") (pin "40") (pinfunction "GND_40") (pintype "power_in"))
      (node (ref "ESP32 S3") (pin "41_1") (pinfunction "GND_41_1") (pintype "power_in"))
      (node (ref "ESP32 S3") (pin "41_2") (pinfunction "GND_41_2") (pintype "power_in"))
      (node (ref "ESP32 S3") (pin "41_3") (pinfunction "GND_41_3") (pintype "power_in"))
      (node (ref "ESP32 S3") (pin "41_4") (pinfunction "GND_41_4") (pintype "power_in"))
      (node (ref "ESP32 S3") (pin "41_5") (pinfunction "GND_41_5") (pintype "power_in"))
      (node (ref "ESP32 S3") (pin "41_6") (pinfunction "GND_41_6") (pintype "power_in"))
      (node (ref "ESP32 S3") (pin "41_7") (pinfunction "GND_41_7") (pintype "power_in"))
      (node (ref "ESP32 S3") (pin "41_8") (pinfunction "GND_41_8") (pintype "power_in"))
      (node (ref "ESP32 S3") (pin "41_9") (pinfunction "GND_41_9") (pintype "power_in"))
      (node (ref "JOY1") (pin "3_VR1") (pinfunction "3_VR1_3_VR1") (pintype "passive"))
      (node (ref "JOY1") (pin "3_VR2") (pinfunction "3_VR2_3_VR2") (pintype "passive"))
      (node (ref "JOY2") (pin "3_VR1") (pinfunction "3_VR1_3_VR1") (pintype "passive"))
      (node (ref "JOY2") (pin "3_VR2") (pinfunction "3_VR2_3_VR2") (pintype "passive"))
      (node (ref "JOY3") (pin "3_VR1") (pinfunction "3_VR1_3_VR1") (pintype "passive"))
      (node (ref "JOY3") (pin "3_VR2") (pinfunction "3_VR2_3_VR2") (pintype "passive"))
      (node (ref "JOY4") (pin "3_VR1") (pinfunction "3_VR1_3_VR1") (pintype "passive"))
      (node (ref "JOY4") (pin "3_VR2") (pinfunction "3_VR2_3_VR2") (pintype "passive"))
      (node (ref "LDO") (pin "1") (pinfunction "Ground_1") (pintype "power_in"))
      (node (ref "LoRa") (pin "1") (pinfunction "GND_1") (pintype "power_in"))
      (node (ref "LoRa") (pin "16") (pinfunction "GND_16") (pintype "power_in"))
      (node (ref "LoRa") (pin "2") (pinfunction "GND_2") (pintype "power_in"))
      (node (ref "LoRa") (pin "9") (pinfunction "GND_9") (pintype "power_in"))
      (node (ref "R10") (pin "1") (pinfunction "1_1") (pintype "passive"))
      (node (ref "R14") (pin "1") (pinfunction "1_1") (pintype "passive"))
      (node (ref "R15") (pin "2") (pinfunction "2_2") (pintype "passive"))
      (node (ref "R16") (pin "2") (pinfunction "2_2") (pintype "passive"))
      (node (ref "R17") (pin "1") (pinfunction "1_1") (pintype "passive"))
      (node (ref "R18") (pin "1") (pinfunction "1_1") (pintype "passive"))
      (node (ref "R19") (pin "2") (pinfunction "2_2") (pintype "passive"))
      (node (ref "R20") (pin "1") (pinfunction "1_1") (pintype "passive"))
      (node (ref "R21") (pin "1") (pinfunction "1_1") (pintype "passive"))
      (node (ref "R22") (pin "2") (pinfunction "2_2") (pintype "passive"))
      (node (ref "R23") (pin "2") (pinfunction "2_2") (pintype "passive"))
      (node (ref "R24") (pin "1") (pinfunction "1_1") (pintype "passive"))
      (node (ref "R6") (pin "1") (pinfunction "1_1") (pintype "passive"))
      (node (ref "R8") (pin "1") (pinfunction "1_1") (pintype "passive"))
      (node (ref "R9") (pin "1") (pinfunction "1_1") (pintype "passive"))
      (node (ref "RESET") (pin "2") (pinfunction "2_2") (pintype "passive"))
      (node (ref "S1") (pin "3") (pinfunction "3_3") (pintype "passive"))
      (node (ref "S2") (pin "3") (pinfunction "3_3") (pintype "passive"))
      (node (ref "SW_PWR") (pin "1") (pinfunction "1_1") (pintype "passive"))
      (node (ref "USB micro B") (pin "5") (pinfunction "GND_5") (pintype "passive"))
    )
    (net (code "38") (name "Net-(ADC1-ADDR)") (class "Default")
      (node (ref "ADC1") (pin "1") (pinfunction "ADDR_1") (pintype "input"))
      (node (ref "R4") (pin "1") (pinfunction "1_1") (pintype "passive"))
    )
    (net (code "39") (name "Net-(ADC1-ALERT{slash}RDY)") (class "Default")
      (node (ref "ADC1") (pin "2") (pinfunction "ALERT/RDY_2") (pintype "open_collector"))
      (node (ref "R5") (pin "1") (pinfunction "1_1") (pintype "passive"))
    )
    (net (code "40") (name "Net-(ADC2-ADDR)") (class "Default")
      (node (ref "ADC2") (pin "1") (pinfunction "ADDR_1") (pintype "input"))
      (node (ref "R13") (pin "1") (pinfunction "1_1") (pintype "passive"))
    )
    (net (code "41") (name "Net-(ADC2-ALERT{slash}RDY)") (class "Default")
      (node (ref "ADC2") (pin "2") (pinfunction "ALERT/RDY_2") (pintype "open_collector"))
      (node (ref "R14") (pin "2") (pinfunction "2_2") (pintype "passive"))
    )
    (net (code "42") (name "Net-(C8-Pad2)") (class "Default")
      (node (ref "C8") (pin "2") (pinfunction "2_2") (pintype "passive"))
      (node (ref "R7") (pin "1") (pinfunction "1_1") (pintype "passive"))
      (node (ref "RESET") (pin "4") (pinfunction "4_4") (pintype "passive"))
    )
    (net (code "43") (name "Net-(D1-K)") (class "Default")
      (node (ref "D1") (pin "1") (pinfunction "K_1") (pintype "passive"))
      (node (ref "R16") (pin "1") (pinfunction "1_1") (pintype "passive"))
    )
    (net (code "44") (name "Net-(D2-K)") (class "Default")
      (node (ref "D2") (pin "1") (pinfunction "K_1") (pintype "passive"))
      (node (ref "R19") (pin "1") (pinfunction "1_1") (pintype "passive"))
    )
    (net (code "45") (name "Net-(D3-K)") (class "Default")
      (node (ref "D3") (pin "1") (pinfunction "K_1") (pintype "passive"))
      (node (ref "R22") (pin "1") (pinfunction "1_1") (pintype "passive"))
    )
    (net (code "46") (name "Net-(D4-K)") (class "Default")
      (node (ref "D4") (pin "1") (pinfunction "K_1") (pintype "passive"))
      (node (ref "R23") (pin "1") (pinfunction "1_1") (pintype "passive"))
    )
    (net (code "47") (name "Net-(D_PWR-K)") (class "Default")
      (node (ref "D_PWR") (pin "1") (pinfunction "K_1") (pintype "passive"))
      (node (ref "R15") (pin "1") (pinfunction "1_1") (pintype "passive"))
    )
    (net (code "48") (name "Net-(ESP32 S3-EN)") (class "Default")
      (node (ref "C2") (pin "1") (pinfunction "1_1") (pintype "passive"))
      (node (ref "ESP32 S3") (pin "3") (pinfunction "EN_3") (pintype "input"))
      (node (ref "R1") (pin "2") (pinfunction "2_2") (pintype "passive"))
    )
    (net (code "49") (name "Net-(LDO-VIN)") (class "Default")
      (node (ref "LDO") (pin "3") (pinfunction "VIN_3") (pintype "power_in"))
      (node (ref "SW_PWR") (pin "2") (pinfunction "2_2") (pintype "passive"))
    )
    (net (code "50") (name "unconnected-(ESP32 S3-IO0-Pad27)") (class "Default")
      (node (ref "ESP32 S3") (pin "27") (pinfunction "IO0_27") (pintype "bidirectional+no_connect"))
    )
    (net (code "51") (name "unconnected-(ESP32 S3-IO1-Pad39)") (class "Default")
      (node (ref "ESP32 S3") (pin "39") (pinfunction "IO1_39") (pintype "bidirectional"))
    )
    (net (code "52") (name "unconnected-(ESP32 S3-IO2-Pad38)") (class "Default")
      (node (ref "ESP32 S3") (pin "38") (pinfunction "IO2_38") (pintype "bidirectional"))
    )
    (net (code "53") (name "unconnected-(ESP32 S3-IO3-Pad15)") (class "Default")
      (node (ref "ESP32 S3") (pin "15") (pinfunction "IO3_15") (pintype "bidirectional+no_connect"))
    )
    (net (code "54") (name "unconnected-(ESP32 S3-IO4-Pad4)") (class "Default")
      (node (ref "ESP32 S3") (pin "4") (pinfunction "IO4_4") (pintype "bidirectional"))
    )
    (net (code "55") (name "unconnected-(ESP32 S3-IO8-Pad12)") (class "Default")
      (node (ref "ESP32 S3") (pin "12") (pinfunction "IO8_12") (pintype "bidirectional"))
    )
    (net (code "56") (name "unconnected-(ESP32 S3-IO14-Pad22)") (class "Default")
      (node (ref "ESP32 S3") (pin "22") (pinfunction "IO14_22") (pintype "bidirectional"))
    )
    (net (code "57") (name "unconnected-(ESP32 S3-IO41-Pad34)") (class "Default")
      (node (ref "ESP32 S3") (pin "34") (pinfunction "IO41_34") (pintype "bidirectional"))
    )
    (net (code "58") (name "unconnected-(ESP32 S3-IO42-Pad35)") (class "Default")
      (node (ref "ESP32 S3") (pin "35") (pinfunction "IO42_35") (pintype "bidirectional"))
    )
    (net (code "59") (name "unconnected-(ESP32 S3-IO45-Pad26)") (class "Default")
      (node (ref "ESP32 S3") (pin "26") (pinfunction "IO45_26") (pintype "bidirectional+no_connect"))
    )
    (net (code "60") (name "unconnected-(ESP32 S3-IO46-Pad16)") (class "Default")
      (node (ref "ESP32 S3") (pin "16") (pinfunction "IO46_16") (pintype "bidirectional+no_connect"))
    )
    (net (code "61") (name "unconnected-(ESP32 S3-IO47-Pad24)") (class "Default")
      (node (ref "ESP32 S3") (pin "24") (pinfunction "IO47_24") (pintype "bidirectional"))
    )
    (net (code "62") (name "unconnected-(ESP32 S3-IO48-Pad25)") (class "Default")
      (node (ref "ESP32 S3") (pin "25") (pinfunction "IO48_25") (pintype "bidirectional"))
    )
    (net (code "63") (name "unconnected-(ESP32 S3-RXD0-Pad36)") (class "Default")
      (node (ref "ESP32 S3") (pin "36") (pinfunction "RXD0_36") (pintype "bidirectional"))
    )
    (net (code "64") (name "unconnected-(ESP32 S3-TXD0-Pad37)") (class "Default")
      (node (ref "ESP32 S3") (pin "37") (pinfunction "TXD0_37") (pintype "bidirectional"))
    )
    (net (code "65") (name "unconnected-(JOY1-MNT_1-Pad1)") (class "Default")
      (node (ref "JOY1") (pin "1") (pinfunction "MNT_1_1") (pintype "passive"))
    )
    (net (code "66") (name "unconnected-(JOY1-MNT_2-Pad2)") (class "Default")
      (node (ref "JOY1") (pin "2") (pinfunction "MNT_2_2") (pintype "passive"))
    )
    (net (code "67") (name "unconnected-(JOY1-MNT_3-Pad3)") (class "Default")
      (node (ref "JOY1") (pin "3") (pinfunction "MNT_3_3") (pintype "passive"))
    )
    (net (code "68") (name "unconnected-(JOY1-MNT_4-Pad4)") (class "Default")
      (node (ref "JOY1") (pin "4") (pinfunction "MNT_4_4") (pintype "passive"))
    )
    (net (code "69") (name "unconnected-(JOY1-Padb)") (class "Default")
      (node (ref "JOY1") (pin "b") (pinfunction "b_b") (pintype "passive"))
    )
    (net (code "70") (name "unconnected-(JOY1-Padd)") (class "Default")
      (node (ref "JOY1") (pin "d") (pinfunction "d_d") (pintype "passive"))
    )
    (net (code "71") (name "unconnected-(JOY2-MNT_1-Pad1)") (class "Default")
      (node (ref "JOY2") (pin "1") (pinfunction "MNT_1_1") (pintype "passive"))
    )
    (net (code "72") (name "unconnected-(JOY2-MNT_2-Pad2)") (class "Default")
      (node (ref "JOY2") (pin "2") (pinfunction "MNT_2_2") (pintype "passive"))
    )
    (net (code "73") (name "unconnected-(JOY2-MNT_3-Pad3)") (class "Default")
      (node (ref "JOY2") (pin "3") (pinfunction "MNT_3_3") (pintype "passive"))
    )
    (net (code "74") (name "unconnected-(JOY2-MNT_4-Pad4)") (class "Default")
      (node (ref "JOY2") (pin "4") (pinfunction "MNT_4_4") (pintype "passive"))
    )
    (net (code "75") (name "unconnected-(JOY2-Padb)") (class "Default")
      (node (ref "JOY2") (pin "b") (pinfunction "b_b") (pintype "passive"))
    )
    (net (code "76") (name "unconnected-(JOY2-Padd)") (class "Default")
      (node (ref "JOY2") (pin "d") (pinfunction "d_d") (pintype "passive"))
    )
    (net (code "77") (name "unconnected-(JOY3-MNT_1-Pad1)") (class "Default")
      (node (ref "JOY3") (pin "1") (pinfunction "MNT_1_1") (pintype "passive"))
    )
    (net (code "78") (name "unconnected-(JOY3-MNT_2-Pad2)") (class "Default")
      (node (ref "JOY3") (pin "2") (pinfunction "MNT_2_2") (pintype "passive"))
    )
    (net (code "79") (name "unconnected-(JOY3-MNT_3-Pad3)") (class "Default")
      (node (ref "JOY3") (pin "3") (pinfunction "MNT_3_3") (pintype "passive"))
    )
    (net (code "80") (name "unconnected-(JOY3-MNT_4-Pad4)") (class "Default")
      (node (ref "JOY3") (pin "4") (pinfunction "MNT_4_4") (pintype "passive"))
    )
    (net (code "81") (name "unconnected-(JOY3-Padb)") (class "Default")
      (node (ref "JOY3") (pin "b") (pinfunction "b_b") (pintype "passive"))
    )
    (net (code "82") (name "unconnected-(JOY3-Padd)") (class "Default")
      (node (ref "JOY3") (pin "d") (pinfunction "d_d") (pintype "passive"))
    )
    (net (code "83") (name "unconnected-(JOY4-MNT_1-Pad1)") (class "Default")
      (node (ref "JOY4") (pin "1") (pinfunction "MNT_1_1") (pintype "passive"))
    )
    (net (code "84") (name "unconnected-(JOY4-MNT_2-Pad2)") (class "Default")
      (node (ref "JOY4") (pin "2") (pinfunction "MNT_2_2") (pintype "passive"))
    )
    (net (code "85") (name "unconnected-(JOY4-MNT_3-Pad3)") (class "Default")
      (node (ref "JOY4") (pin "3") (pinfunction "MNT_3_3") (pintype "passive"))
    )
    (net (code "86") (name "unconnected-(JOY4-MNT_4-Pad4)") (class "Default")
      (node (ref "JOY4") (pin "4") (pinfunction "MNT_4_4") (pintype "passive"))
    )
    (net (code "87") (name "unconnected-(JOY4-Padb)") (class "Default")
      (node (ref "JOY4") (pin "b") (pinfunction "b_b") (pintype "passive"))
    )
    (net (code "88") (name "unconnected-(JOY4-Padd)") (class "Default")
      (node (ref "JOY4") (pin "d") (pinfunction "d_d") (pintype "passive"))
    )
    (net (code "89") (name "unconnected-(LDO-VOUT-Pad4)") (class "Default")
      (node (ref "LDO") (pin "4") (pinfunction "VOUT_4") (pintype "passive"))
    )
    (net (code "90") (name "unconnected-(LoRa-DI01-Pad6)") (class "Default")
      (node (ref "LoRa") (pin "6") (pinfunction "DI01_6") (pintype "bidirectional"))
    )
    (net (code "91") (name "unconnected-(LoRa-DI02-Pad7)") (class "Default")
      (node (ref "LoRa") (pin "7") (pinfunction "DI02_7") (pintype "bidirectional"))
    )
    (net (code "92") (name "unconnected-(LoRa-DI03-Pad8)") (class "Default")
      (node (ref "LoRa") (pin "8") (pinfunction "DI03_8") (pintype "bidirectional"))
    )
    (net (code "93") (name "unconnected-(LoRa-DI04-Pad10)") (class "Default")
      (node (ref "LoRa") (pin "10") (pinfunction "DI04_10") (pintype "bidirectional"))
    )
    (net (code "94") (name "unconnected-(LoRa-DI05-Pad11)") (class "Default")
      (node (ref "LoRa") (pin "11") (pinfunction "DI05_11") (pintype "bidirectional"))
    )
    (net (code "95") (name "unconnected-(RESET-Pad1)") (class "Default")
      (node (ref "RESET") (pin "1") (pinfunction "1_1") (pintype "passive"))
    )
    (net (code "96") (name "unconnected-(RESET-Pad3)") (class "Default")
      (node (ref "RESET") (pin "3") (pinfunction "3_3") (pintype "passive"))
    )
    (net (code "97") (name "unconnected-(SW1-PadA')") (class "Default")
      (node (ref "SW1") (pin "A'") (pinfunction "A'_A'") (pintype "passive"))
    )
    (net (code "98") (name "unconnected-(SW1-PadB)") (class "Default")
      (node (ref "SW1") (pin "B") (pinfunction "B_B") (pintype "passive"))
    )
    (net (code "99") (name "unconnected-(SW2-PadA')") (class "Default")
      (node (ref "SW2") (pin "A'") (pinfunction "A'_A'") (pintype "passive"))
    )
    (net (code "100") (name "unconnected-(SW2-PadB)") (class "Default")
      (node (ref "SW2") (pin "B") (pinfunction "B_B") (pintype "passive"))
    )
    (net (code "101") (name "unconnected-(SW3-PadA')") (class "Default")
      (node (ref "SW3") (pin "A'") (pinfunction "A'_A'") (pintype "passive"))
    )
    (net (code "102") (name "unconnected-(SW3-PadB)") (class "Default")
      (node (ref "SW3") (pin "B") (pinfunction "B_B") (pintype "passive"))
    )
    (net (code "103") (name "unconnected-(SW4-PadA')") (class "Default")
      (node (ref "SW4") (pin "A'") (pinfunction "A'_A'") (pintype "passive"))
    )
    (net (code "104") (name "unconnected-(SW4-PadB)") (class "Default")
      (node (ref "SW4") (pin "B") (pinfunction "B_B") (pintype "passive"))
    )
    (net (code "105") (name "unconnected-(SW5-PadA')") (class "Default")
      (node (ref "SW5") (pin "A'") (pinfunction "A'_A'") (pintype "passive"))
    )
    (net (code "106") (name "unconnected-(SW5-PadB)") (class "Default")
      (node (ref "SW5") (pin "B") (pinfunction "B_B") (pintype "passive"))
    )
    (net (code "107") (name "unconnected-(USB micro B-ID-Pad4)") (class "Default")
      (node (ref "USB micro B") (pin "4") (pinfunction "ID_4") (pintype "passive"))
    )
    (net (code "108") (name "unconnected-(USB micro B-SHLD1-Pad6)") (class "Default")
      (node (ref "USB micro B") (pin "6") (pinfunction "SHLD1_6") (pintype "passive"))
    )
    (net (code "109") (name "unconnected-(USB micro B-SHLD2-Pad7)") (class "Default")
      (node (ref "USB micro B") (pin "7") (pinfunction "SHLD2_7") (pintype "passive"))
    )
    (net (code "110") (name "unconnected-(USB micro B-SHLD3-Pad8)") (class "Default")
      (node (ref "USB micro B") (pin "8") (pinfunction "SHLD3_8") (pintype "passive"))
    )
    (net (code "111") (name "unconnected-(USB micro B-SHLD4-Pad9)") (class "Default")
      (node (ref "USB micro B") (pin "9") (pinfunction "SHLD4_9") (pintype "passive"))
    )
    (net (code "112") (name "unconnected-(USB micro B-SHLD5-Pad10)") (class "Default")
      (node (ref "USB micro B") (pin "10") (pinfunction "SHLD5_10") (pintype "passive"))
    )
    (net (code "113") (name "unconnected-(USB micro B-SHLD6-Pad11)") (class "Default")
      (node (ref "USB micro B") (pin "11") (pinfunction "SHLD6_11") (pintype "passive"))
    )
    (net (code "114") (name "unconnected-(USB micro B-VBUS-Pad1)") (class "Default")
      (node (ref "USB micro B") (pin "1") (pinfunction "VBUS_1") (pintype "passive"))
    )
  )
)
